# IRN.net
KiCad netlist of a schematic drawn in Altium Designer
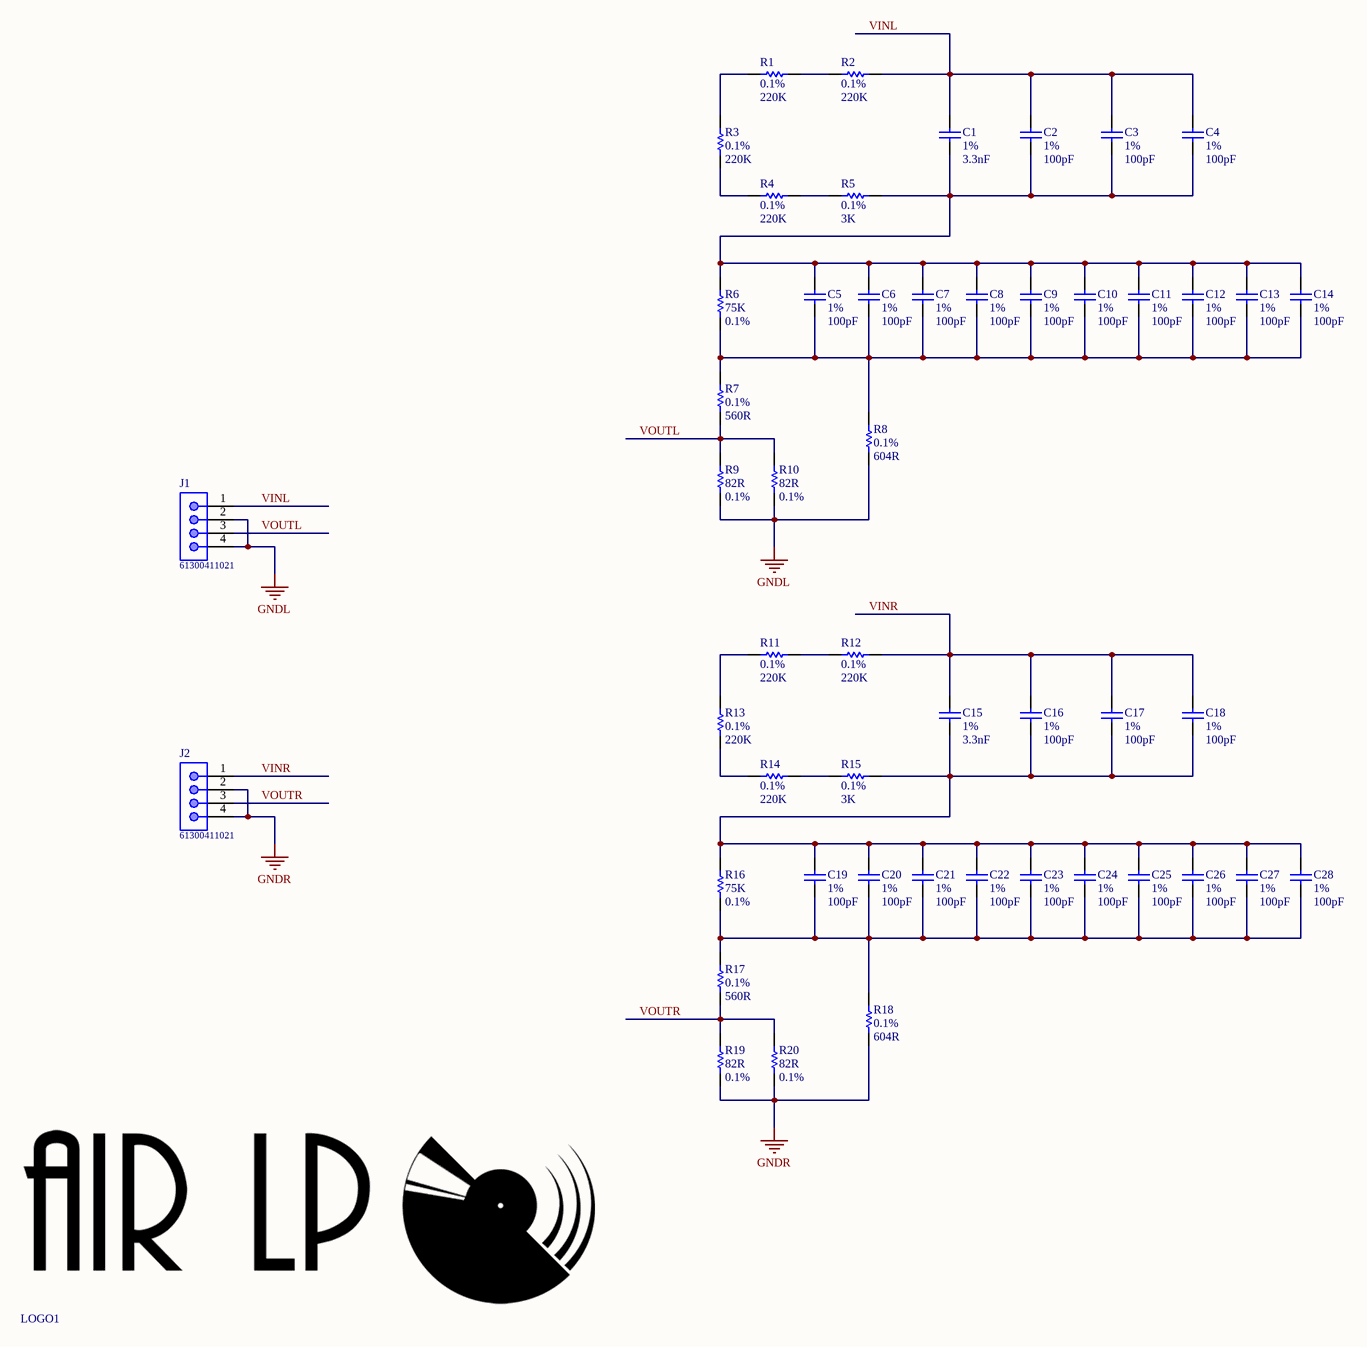
[diagram p0: IRN.SchDoc]

(export (version "E")
  (design (tool "Eeschema 10.0.6"))
  (components
    (comp (ref "C1")
      (value "3.3nF")
      (footprint "CAPC0603(1608)100_L")
      (description "0603 (1608 Metric) Chip Capacitor")
      (fields (field (name "TOLERANCE") "1%") (field (name "Comment") "CAP0603"))
      (libsource (lib "Altium Content Vault") (part "CAP_5"))
    )
    (comp (ref "C2")
      (value "100pF")
      (footprint "CAPC0603(1608)100_L")
      (description "0603 (1608 Metric) Chip Capacitor")
      (fields (field (name "TOLERANCE") "1%") (field (name "Comment") "CAP0603"))
      (libsource (lib "Altium Content Vault") (part "CAP_5"))
    )
    (comp (ref "C3")
      (value "100pF")
      (footprint "CAPC0603(1608)100_L")
      (description "0603 (1608 Metric) Chip Capacitor")
      (fields (field (name "TOLERANCE") "1%") (field (name "Comment") "CAP0603"))
      (libsource (lib "Altium Content Vault") (part "CAP_5"))
    )
    (comp (ref "C4")
      (value "100pF")
      (footprint "CAPC0603(1608)100_L")
      (description "0603 (1608 Metric) Chip Capacitor")
      (fields (field (name "TOLERANCE") "1%") (field (name "Comment") "CAP0603"))
      (libsource (lib "Altium Content Vault") (part "CAP_5"))
    )
    (comp (ref "C5")
      (value "100pF")
      (footprint "CAPC0603(1608)100_L")
      (description "0603 (1608 Metric) Chip Capacitor")
      (fields (field (name "TOLERANCE") "1%") (field (name "Comment") "CAP0603"))
      (libsource (lib "Altium Content Vault") (part "CAP_5"))
    )
    (comp (ref "C6")
      (value "100pF")
      (footprint "CAPC0603(1608)100_L")
      (description "0603 (1608 Metric) Chip Capacitor")
      (fields (field (name "TOLERANCE") "1%") (field (name "Comment") "CAP0603"))
      (libsource (lib "Altium Content Vault") (part "CAP_5"))
    )
    (comp (ref "C7")
      (value "100pF")
      (footprint "CAPC0603(1608)100_L")
      (description "0603 (1608 Metric) Chip Capacitor")
      (fields (field (name "TOLERANCE") "1%") (field (name "Comment") "CAP0603"))
      (libsource (lib "Altium Content Vault") (part "CAP_5"))
    )
    (comp (ref "C8")
      (value "100pF")
      (footprint "CAPC0603(1608)100_L")
      (description "0603 (1608 Metric) Chip Capacitor")
      (fields (field (name "TOLERANCE") "1%") (field (name "Comment") "CAP0603"))
      (libsource (lib "Altium Content Vault") (part "CAP_5"))
    )
    (comp (ref "C9")
      (value "100pF")
      (footprint "CAPC0603(1608)100_L")
      (description "0603 (1608 Metric) Chip Capacitor")
      (fields (field (name "TOLERANCE") "1%") (field (name "Comment") "CAP0603"))
      (libsource (lib "Altium Content Vault") (part "CAP_5"))
    )
    (comp (ref "C10")
      (value "100pF")
      (footprint "CAPC0603(1608)100_L")
      (description "0603 (1608 Metric) Chip Capacitor")
      (fields (field (name "TOLERANCE") "1%") (field (name "Comment") "CAP0603"))
      (libsource (lib "Altium Content Vault") (part "CAP_5"))
    )
    (comp (ref "C11")
      (value "100pF")
      (footprint "CAPC0603(1608)100_L")
      (description "0603 (1608 Metric) Chip Capacitor")
      (fields (field (name "TOLERANCE") "1%") (field (name "Comment") "CAP0603"))
      (libsource (lib "Altium Content Vault") (part "CAP_5"))
    )
    (comp (ref "C12")
      (value "100pF")
      (footprint "CAPC0603(1608)100_L")
      (description "0603 (1608 Metric) Chip Capacitor")
      (fields (field (name "TOLERANCE") "1%") (field (name "Comment") "CAP0603"))
      (libsource (lib "Altium Content Vault") (part "CAP_5"))
    )
    (comp (ref "C13")
      (value "100pF")
      (footprint "CAPC0603(1608)100_L")
      (description "0603 (1608 Metric) Chip Capacitor")
      (fields (field (name "TOLERANCE") "1%") (field (name "Comment") "CAP0603"))
      (libsource (lib "Altium Content Vault") (part "CAP_5"))
    )
    (comp (ref "C14")
      (value "100pF")
      (footprint "CAPC0603(1608)100_L")
      (description "0603 (1608 Metric) Chip Capacitor")
      (fields (field (name "TOLERANCE") "1%") (field (name "Comment") "CAP0603"))
      (libsource (lib "Altium Content Vault") (part "CAP_5"))
    )
    (comp (ref "C15")
      (value "3.3nF")
      (footprint "CAPC0603(1608)100_L")
      (description "0603 (1608 Metric) Chip Capacitor")
      (fields (field (name "TOLERANCE") "1%") (field (name "Comment") "CAP0603"))
      (libsource (lib "Altium Content Vault") (part "CAP_5"))
    )
    (comp (ref "C16")
      (value "100pF")
      (footprint "CAPC0603(1608)100_L")
      (description "0603 (1608 Metric) Chip Capacitor")
      (fields (field (name "TOLERANCE") "1%") (field (name "Comment") "CAP0603"))
      (libsource (lib "Altium Content Vault") (part "CAP_5"))
    )
    (comp (ref "C17")
      (value "100pF")
      (footprint "CAPC0603(1608)100_L")
      (description "0603 (1608 Metric) Chip Capacitor")
      (fields (field (name "TOLERANCE") "1%") (field (name "Comment") "CAP0603"))
      (libsource (lib "Altium Content Vault") (part "CAP_5"))
    )
    (comp (ref "C18")
      (value "100pF")
      (footprint "CAPC0603(1608)100_L")
      (description "0603 (1608 Metric) Chip Capacitor")
      (fields (field (name "TOLERANCE") "1%") (field (name "Comment") "CAP0603"))
      (libsource (lib "Altium Content Vault") (part "CAP_5"))
    )
    (comp (ref "C19")
      (value "100pF")
      (footprint "CAPC0603(1608)100_L")
      (description "0603 (1608 Metric) Chip Capacitor")
      (fields (field (name "TOLERANCE") "1%") (field (name "Comment") "CAP0603"))
      (libsource (lib "Altium Content Vault") (part "CAP_5"))
    )
    (comp (ref "C20")
      (value "100pF")
      (footprint "CAPC0603(1608)100_L")
      (description "0603 (1608 Metric) Chip Capacitor")
      (fields (field (name "TOLERANCE") "1%") (field (name "Comment") "CAP0603"))
      (libsource (lib "Altium Content Vault") (part "CAP_5"))
    )
    (comp (ref "C21")
      (value "100pF")
      (footprint "CAPC0603(1608)100_L")
      (description "0603 (1608 Metric) Chip Capacitor")
      (fields (field (name "TOLERANCE") "1%") (field (name "Comment") "CAP0603"))
      (libsource (lib "Altium Content Vault") (part "CAP_5"))
    )
    (comp (ref "C22")
      (value "100pF")
      (footprint "CAPC0603(1608)100_L")
      (description "0603 (1608 Metric) Chip Capacitor")
      (fields (field (name "TOLERANCE") "1%") (field (name "Comment") "CAP0603"))
      (libsource (lib "Altium Content Vault") (part "CAP_5"))
    )
    (comp (ref "C23")
      (value "100pF")
      (footprint "CAPC0603(1608)100_L")
      (description "0603 (1608 Metric) Chip Capacitor")
      (fields (field (name "TOLERANCE") "1%") (field (name "Comment") "CAP0603"))
      (libsource (lib "Altium Content Vault") (part "CAP_5"))
    )
    (comp (ref "C24")
      (value "100pF")
      (footprint "CAPC0603(1608)100_L")
      (description "0603 (1608 Metric) Chip Capacitor")
      (fields (field (name "TOLERANCE") "1%") (field (name "Comment") "CAP0603"))
      (libsource (lib "Altium Content Vault") (part "CAP_5"))
    )
    (comp (ref "C25")
      (value "100pF")
      (footprint "CAPC0603(1608)100_L")
      (description "0603 (1608 Metric) Chip Capacitor")
      (fields (field (name "TOLERANCE") "1%") (field (name "Comment") "CAP0603"))
      (libsource (lib "Altium Content Vault") (part "CAP_5"))
    )
    (comp (ref "C26")
      (value "100pF")
      (footprint "CAPC0603(1608)100_L")
      (description "0603 (1608 Metric) Chip Capacitor")
      (fields (field (name "TOLERANCE") "1%") (field (name "Comment") "CAP0603"))
      (libsource (lib "Altium Content Vault") (part "CAP_5"))
    )
    (comp (ref "C27")
      (value "100pF")
      (footprint "CAPC0603(1608)100_L")
      (description "0603 (1608 Metric) Chip Capacitor")
      (fields (field (name "TOLERANCE") "1%") (field (name "Comment") "CAP0603"))
      (libsource (lib "Altium Content Vault") (part "CAP_5"))
    )
    (comp (ref "C28")
      (value "100pF")
      (footprint "CAPC0603(1608)100_L")
      (description "0603 (1608 Metric) Chip Capacitor")
      (fields (field (name "TOLERANCE") "1%") (field (name "Comment") "CAP0603"))
      (libsource (lib "Altium Content Vault") (part "CAP_5"))
    )
    (comp (ref "J1")
      (value "61300411021")
      (footprint "61300411021")
      (description "THT Angled Pin Header WR-PHD, Pitch 2.54 mm, Single Row, 4 pins")
      (fields (field (name "PUBLISHER") "Wurth Elektronik"))
      (libsource (lib "altium-import") (part "root_0_mirrored_61300411021_"))
    )
    (comp (ref "J2")
      (value "61300411021")
      (footprint "61300411021")
      (description "THT Angled Pin Header WR-PHD, Pitch 2.54 mm, Single Row, 4 pins")
      (fields (field (name "PUBLISHER") "Wurth Elektronik"))
      (libsource (lib "altium-import") (part "root_0_mirrored_61300411021_"))
    )
    (comp (ref "LOGO1")
      (value "LOGO-AIRLP")
      (footprint "LOGO-AIR-LP")
      (description "LOGO AIR LP")
      (libsource (lib "micun") (part "LOGO-AIRLP"))
    )
    (comp (ref "R1")
      (value "220K")
      (footprint "RESC0805(2012)_L")
      (description "0805 (2012 Metric) Chip Resistor")
      (fields (field (name "TOLERANCE") "0.1%") (field (name "Comment") "RES0805"))
      (libsource (lib "Altium Content Vault") (part "RES_3"))
    )
    (comp (ref "R2")
      (value "220K")
      (footprint "RESC0805(2012)_L")
      (description "0805 (2012 Metric) Chip Resistor")
      (fields (field (name "TOLERANCE") "0.1%") (field (name "Comment") "RES0805"))
      (libsource (lib "Altium Content Vault") (part "RES_3"))
    )
    (comp (ref "R3")
      (value "220K")
      (footprint "RESC0805(2012)_L")
      (description "0805 (2012 Metric) Chip Resistor")
      (fields (field (name "TOLERANCE") "0.1%") (field (name "Comment") "RES0805"))
      (libsource (lib "Altium Content Vault") (part "RES_3"))
    )
    (comp (ref "R4")
      (value "220K")
      (footprint "RESC0805(2012)_L")
      (description "0805 (2012 Metric) Chip Resistor")
      (fields (field (name "TOLERANCE") "0.1%") (field (name "Comment") "RES0805"))
      (libsource (lib "Altium Content Vault") (part "RES_3"))
    )
    (comp (ref "R5")
      (value "3K")
      (footprint "RESC0805(2012)_L")
      (description "0805 (2012 Metric) Chip Resistor")
      (fields (field (name "TOLERANCE") "0.1%") (field (name "Comment") "RES0805"))
      (libsource (lib "Altium Content Vault") (part "RES_3"))
    )
    (comp (ref "R6")
      (value "75K")
      (footprint "RESC0603(1608)_L")
      (description "0603 (1608 Metric) Chip Resistor")
      (fields (field (name "TOLERANCE") "0.1%") (field (name "Comment") "RES0603"))
      (libsource (lib "Altium Content Vault") (part "RES_3"))
    )
    (comp (ref "R7")
      (value "560R")
      (footprint "RESC0805(2012)_L")
      (description "0805 (2012 Metric) Chip Resistor")
      (fields (field (name "TOLERANCE") "0.1%") (field (name "Comment") "RES0805"))
      (libsource (lib "Altium Content Vault") (part "RES_3"))
    )
    (comp (ref "R8")
      (value "604R")
      (footprint "RESC0805(2012)_L")
      (description "0805 (2012 Metric) Chip Resistor")
      (fields (field (name "TOLERANCE") "0.1%") (field (name "Comment") "RES0805"))
      (libsource (lib "Altium Content Vault") (part "RES_3"))
    )
    (comp (ref "R9")
      (value "82R")
      (footprint "RESC0603(1608)_L")
      (description "0603 (1608 Metric) Chip Resistor")
      (fields (field (name "TOLERANCE") "0.1%") (field (name "Comment") "RES0603"))
      (libsource (lib "Altium Content Vault") (part "RES_3"))
    )
    (comp (ref "R10")
      (value "82R")
      (footprint "RESC0603(1608)_L")
      (description "0603 (1608 Metric) Chip Resistor")
      (fields (field (name "TOLERANCE") "0.1%") (field (name "Comment") "RES0603"))
      (libsource (lib "Altium Content Vault") (part "RES_3"))
    )
    (comp (ref "R11")
      (value "220K")
      (footprint "RESC0805(2012)_L")
      (description "0805 (2012 Metric) Chip Resistor")
      (fields (field (name "TOLERANCE") "0.1%") (field (name "Comment") "RES0805"))
      (libsource (lib "Altium Content Vault") (part "RES_3"))
    )
    (comp (ref "R12")
      (value "220K")
      (footprint "RESC0805(2012)_L")
      (description "0805 (2012 Metric) Chip Resistor")
      (fields (field (name "TOLERANCE") "0.1%") (field (name "Comment") "RES0805"))
      (libsource (lib "Altium Content Vault") (part "RES_3"))
    )
    (comp (ref "R13")
      (value "220K")
      (footprint "RESC0805(2012)_L")
      (description "0805 (2012 Metric) Chip Resistor")
      (fields (field (name "TOLERANCE") "0.1%") (field (name "Comment") "RES0805"))
      (libsource (lib "Altium Content Vault") (part "RES_3"))
    )
    (comp (ref "R14")
      (value "220K")
      (footprint "RESC0805(2012)_L")
      (description "0805 (2012 Metric) Chip Resistor")
      (fields (field (name "TOLERANCE") "0.1%") (field (name "Comment") "RES0805"))
      (libsource (lib "Altium Content Vault") (part "RES_3"))
    )
    (comp (ref "R15")
      (value "3K")
      (footprint "RESC0805(2012)_L")
      (description "0805 (2012 Metric) Chip Resistor")
      (fields (field (name "TOLERANCE") "0.1%") (field (name "Comment") "RES0805"))
      (libsource (lib "Altium Content Vault") (part "RES_3"))
    )
    (comp (ref "R16")
      (value "75K")
      (footprint "RESC0603(1608)_L")
      (description "0603 (1608 Metric) Chip Resistor")
      (fields (field (name "TOLERANCE") "0.1%") (field (name "Comment") "RES0603"))
      (libsource (lib "Altium Content Vault") (part "RES_3"))
    )
    (comp (ref "R17")
      (value "560R")
      (footprint "RESC0805(2012)_L")
      (description "0805 (2012 Metric) Chip Resistor")
      (fields (field (name "TOLERANCE") "0.1%") (field (name "Comment") "RES0805"))
      (libsource (lib "Altium Content Vault") (part "RES_3"))
    )
    (comp (ref "R18")
      (value "604R")
      (footprint "RESC0805(2012)_L")
      (description "0805 (2012 Metric) Chip Resistor")
      (fields (field (name "TOLERANCE") "0.1%") (field (name "Comment") "RES0805"))
      (libsource (lib "Altium Content Vault") (part "RES_3"))
    )
    (comp (ref "R19")
      (value "82R")
      (footprint "RESC0603(1608)_L")
      (description "0603 (1608 Metric) Chip Resistor")
      (fields (field (name "TOLERANCE") "0.1%") (field (name "Comment") "RES0603"))
      (libsource (lib "Altium Content Vault") (part "RES_3"))
    )
    (comp (ref "R20")
      (value "82R")
      (footprint "RESC0603(1608)_L")
      (description "0603 (1608 Metric) Chip Resistor")
      (fields (field (name "TOLERANCE") "0.1%") (field (name "Comment") "RES0603"))
      (libsource (lib "Altium Content Vault") (part "RES_3"))
    )
  )
  (nets
    (net (code "1") (name "/VINL") (class "Default")
      (node (ref "C1") (pin "2") (pinfunction "2_2") (pintype "passive"))
      (node (ref "C2") (pin "2") (pinfunction "2_2") (pintype "passive"))
      (node (ref "C3") (pin "2") (pinfunction "2_2") (pintype "passive"))
      (node (ref "C4") (pin "2") (pinfunction "2_2") (pintype "passive"))
      (node (ref "J1") (pin "1") (pinfunction "1_1") (pintype "passive"))
      (node (ref "R2") (pin "2") (pinfunction "2_2") (pintype "passive"))
    )
    (net (code "2") (name "/VINR") (class "Default")
      (node (ref "C15") (pin "2") (pinfunction "2_2") (pintype "passive"))
      (node (ref "C16") (pin "2") (pinfunction "2_2") (pintype "passive"))
      (node (ref "C17") (pin "2") (pinfunction "2_2") (pintype "passive"))
      (node (ref "C18") (pin "2") (pinfunction "2_2") (pintype "passive"))
      (node (ref "J2") (pin "1") (pinfunction "1_1") (pintype "passive"))
      (node (ref "R12") (pin "2") (pinfunction "2_2") (pintype "passive"))
    )
    (net (code "3") (name "/VOUTL") (class "Default")
      (node (ref "J1") (pin "3") (pinfunction "3_3") (pintype "passive"))
      (node (ref "R10") (pin "1") (pinfunction "1_1") (pintype "passive"))
      (node (ref "R7") (pin "2") (pinfunction "2_2") (pintype "passive"))
      (node (ref "R9") (pin "1") (pinfunction "1_1") (pintype "passive"))
    )
    (net (code "4") (name "/VOUTR") (class "Default")
      (node (ref "J2") (pin "3") (pinfunction "3_3") (pintype "passive"))
      (node (ref "R17") (pin "2") (pinfunction "2_2") (pintype "passive"))
      (node (ref "R19") (pin "1") (pinfunction "1_1") (pintype "passive"))
      (node (ref "R20") (pin "1") (pinfunction "1_1") (pintype "passive"))
    )
    (net (code "5") (name "GNDL") (class "Default")
      (node (ref "J1") (pin "2") (pinfunction "2_2") (pintype "passive"))
      (node (ref "J1") (pin "4") (pinfunction "4_4") (pintype "passive"))
      (node (ref "R10") (pin "2") (pinfunction "2_2") (pintype "passive"))
      (node (ref "R8") (pin "2") (pinfunction "2_2") (pintype "passive"))
      (node (ref "R9") (pin "2") (pinfunction "2_2") (pintype "passive"))
    )
    (net (code "6") (name "GNDR") (class "Default")
      (node (ref "J2") (pin "2") (pinfunction "2_2") (pintype "passive"))
      (node (ref "J2") (pin "4") (pinfunction "4_4") (pintype "passive"))
      (node (ref "R18") (pin "2") (pinfunction "2_2") (pintype "passive"))
      (node (ref "R19") (pin "2") (pinfunction "2_2") (pintype "passive"))
      (node (ref "R20") (pin "2") (pinfunction "2_2") (pintype "passive"))
    )
    (net (code "7") (name "Net-(C1-Pad1)") (class "Default")
      (node (ref "C1") (pin "1") (pinfunction "1_1") (pintype "passive"))
      (node (ref "C10") (pin "2") (pinfunction "2_2") (pintype "passive"))
      (node (ref "C11") (pin "2") (pinfunction "2_2") (pintype "passive"))
      (node (ref "C12") (pin "2") (pinfunction "2_2") (pintype "passive"))
      (node (ref "C13") (pin "2") (pinfunction "2_2") (pintype "passive"))
      (node (ref "C14") (pin "2") (pinfunction "2_2") (pintype "passive"))
      (node (ref "C2") (pin "1") (pinfunction "1_1") (pintype "passive"))
      (node (ref "C3") (pin "1") (pinfunction "1_1") (pintype "passive"))
      (node (ref "C4") (pin "1") (pinfunction "1_1") (pintype "passive"))
      (node (ref "C5") (pin "2") (pinfunction "2_2") (pintype "passive"))
      (node (ref "C6") (pin "2") (pinfunction "2_2") (pintype "passive"))
      (node (ref "C7") (pin "2") (pinfunction "2_2") (pintype "passive"))
      (node (ref "C8") (pin "2") (pinfunction "2_2") (pintype "passive"))
      (node (ref "C9") (pin "2") (pinfunction "2_2") (pintype "passive"))
      (node (ref "R5") (pin "2") (pinfunction "2_2") (pintype "passive"))
      (node (ref "R6") (pin "1") (pinfunction "1_1") (pintype "passive"))
    )
    (net (code "8") (name "Net-(C10-Pad1)") (class "Default")
      (node (ref "C10") (pin "1") (pinfunction "1_1") (pintype "passive"))
      (node (ref "C11") (pin "1") (pinfunction "1_1") (pintype "passive"))
      (node (ref "C12") (pin "1") (pinfunction "1_1") (pintype "passive"))
      (node (ref "C13") (pin "1") (pinfunction "1_1") (pintype "passive"))
      (node (ref "C14") (pin "1") (pinfunction "1_1") (pintype "passive"))
      (node (ref "C5") (pin "1") (pinfunction "1_1") (pintype "passive"))
      (node (ref "C6") (pin "1") (pinfunction "1_1") (pintype "passive"))
      (node (ref "C7") (pin "1") (pinfunction "1_1") (pintype "passive"))
      (node (ref "C8") (pin "1") (pinfunction "1_1") (pintype "passive"))
      (node (ref "C9") (pin "1") (pinfunction "1_1") (pintype "passive"))
      (node (ref "R6") (pin "2") (pinfunction "2_2") (pintype "passive"))
      (node (ref "R7") (pin "1") (pinfunction "1_1") (pintype "passive"))
      (node (ref "R8") (pin "1") (pinfunction "1_1") (pintype "passive"))
    )
    (net (code "9") (name "Net-(C15-Pad1)") (class "Default")
      (node (ref "C15") (pin "1") (pinfunction "1_1") (pintype "passive"))
      (node (ref "C16") (pin "1") (pinfunction "1_1") (pintype "passive"))
      (node (ref "C17") (pin "1") (pinfunction "1_1") (pintype "passive"))
      (node (ref "C18") (pin "1") (pinfunction "1_1") (pintype "passive"))
      (node (ref "C19") (pin "2") (pinfunction "2_2") (pintype "passive"))
      (node (ref "C20") (pin "2") (pinfunction "2_2") (pintype "passive"))
      (node (ref "C21") (pin "2") (pinfunction "2_2") (pintype "passive"))
      (node (ref "C22") (pin "2") (pinfunction "2_2") (pintype "passive"))
      (node (ref "C23") (pin "2") (pinfunction "2_2") (pintype "passive"))
      (node (ref "C24") (pin "2") (pinfunction "2_2") (pintype "passive"))
      (node (ref "C25") (pin "2") (pinfunction "2_2") (pintype "passive"))
      (node (ref "C26") (pin "2") (pinfunction "2_2") (pintype "passive"))
      (node (ref "C27") (pin "2") (pinfunction "2_2") (pintype "passive"))
      (node (ref "C28") (pin "2") (pinfunction "2_2") (pintype "passive"))
      (node (ref "R15") (pin "2") (pinfunction "2_2") (pintype "passive"))
      (node (ref "R16") (pin "1") (pinfunction "1_1") (pintype "passive"))
    )
    (net (code "10") (name "Net-(C19-Pad1)") (class "Default")
      (node (ref "C19") (pin "1") (pinfunction "1_1") (pintype "passive"))
      (node (ref "C20") (pin "1") (pinfunction "1_1") (pintype "passive"))
      (node (ref "C21") (pin "1") (pinfunction "1_1") (pintype "passive"))
      (node (ref "C22") (pin "1") (pinfunction "1_1") (pintype "passive"))
      (node (ref "C23") (pin "1") (pinfunction "1_1") (pintype "passive"))
      (node (ref "C24") (pin "1") (pinfunction "1_1") (pintype "passive"))
      (node (ref "C25") (pin "1") (pinfunction "1_1") (pintype "passive"))
      (node (ref "C26") (pin "1") (pinfunction "1_1") (pintype "passive"))
      (node (ref "C27") (pin "1") (pinfunction "1_1") (pintype "passive"))
      (node (ref "C28") (pin "1") (pinfunction "1_1") (pintype "passive"))
      (node (ref "R16") (pin "2") (pinfunction "2_2") (pintype "passive"))
      (node (ref "R17") (pin "1") (pinfunction "1_1") (pintype "passive"))
      (node (ref "R18") (pin "1") (pinfunction "1_1") (pintype "passive"))
    )
    (net (code "11") (name "Net-(R1-Pad1)") (class "Default")
      (node (ref "R1") (pin "1") (pinfunction "1_1") (pintype "passive"))
      (node (ref "R3") (pin "1") (pinfunction "1_1") (pintype "passive"))
    )
    (net (code "12") (name "Net-(R1-Pad2)") (class "Default")
      (node (ref "R1") (pin "2") (pinfunction "2_2") (pintype "passive"))
      (node (ref "R2") (pin "1") (pinfunction "1_1") (pintype "passive"))
    )
    (net (code "13") (name "Net-(R3-Pad2)") (class "Default")
      (node (ref "R3") (pin "2") (pinfunction "2_2") (pintype "passive"))
      (node (ref "R4") (pin "1") (pinfunction "1_1") (pintype "passive"))
    )
    (net (code "14") (name "Net-(R4-Pad2)") (class "Default")
      (node (ref "R4") (pin "2") (pinfunction "2_2") (pintype "passive"))
      (node (ref "R5") (pin "1") (pinfunction "1_1") (pintype "passive"))
    )
    (net (code "15") (name "Net-(R11-Pad1)") (class "Default")
      (node (ref "R11") (pin "1") (pinfunction "1_1") (pintype "passive"))
      (node (ref "R13") (pin "1") (pinfunction "1_1") (pintype "passive"))
    )
    (net (code "16") (name "Net-(R11-Pad2)") (class "Default")
      (node (ref "R11") (pin "2") (pinfunction "2_2") (pintype "passive"))
      (node (ref "R12") (pin "1") (pinfunction "1_1") (pintype "passive"))
    )
    (net (code "17") (name "Net-(R13-Pad2)") (class "Default")
      (node (ref "R13") (pin "2") (pinfunction "2_2") (pintype "passive"))
      (node (ref "R14") (pin "1") (pinfunction "1_1") (pintype "passive"))
    )
    (net (code "18") (name "Net-(R14-Pad2)") (class "Default")
      (node (ref "R14") (pin "2") (pinfunction "2_2") (pintype "passive"))
      (node (ref "R15") (pin "1") (pinfunction "1_1") (pintype "passive"))
    )
  )
)
